# medusa-charger.net
KiCad netlist of a schematic drawn in Altium Designer
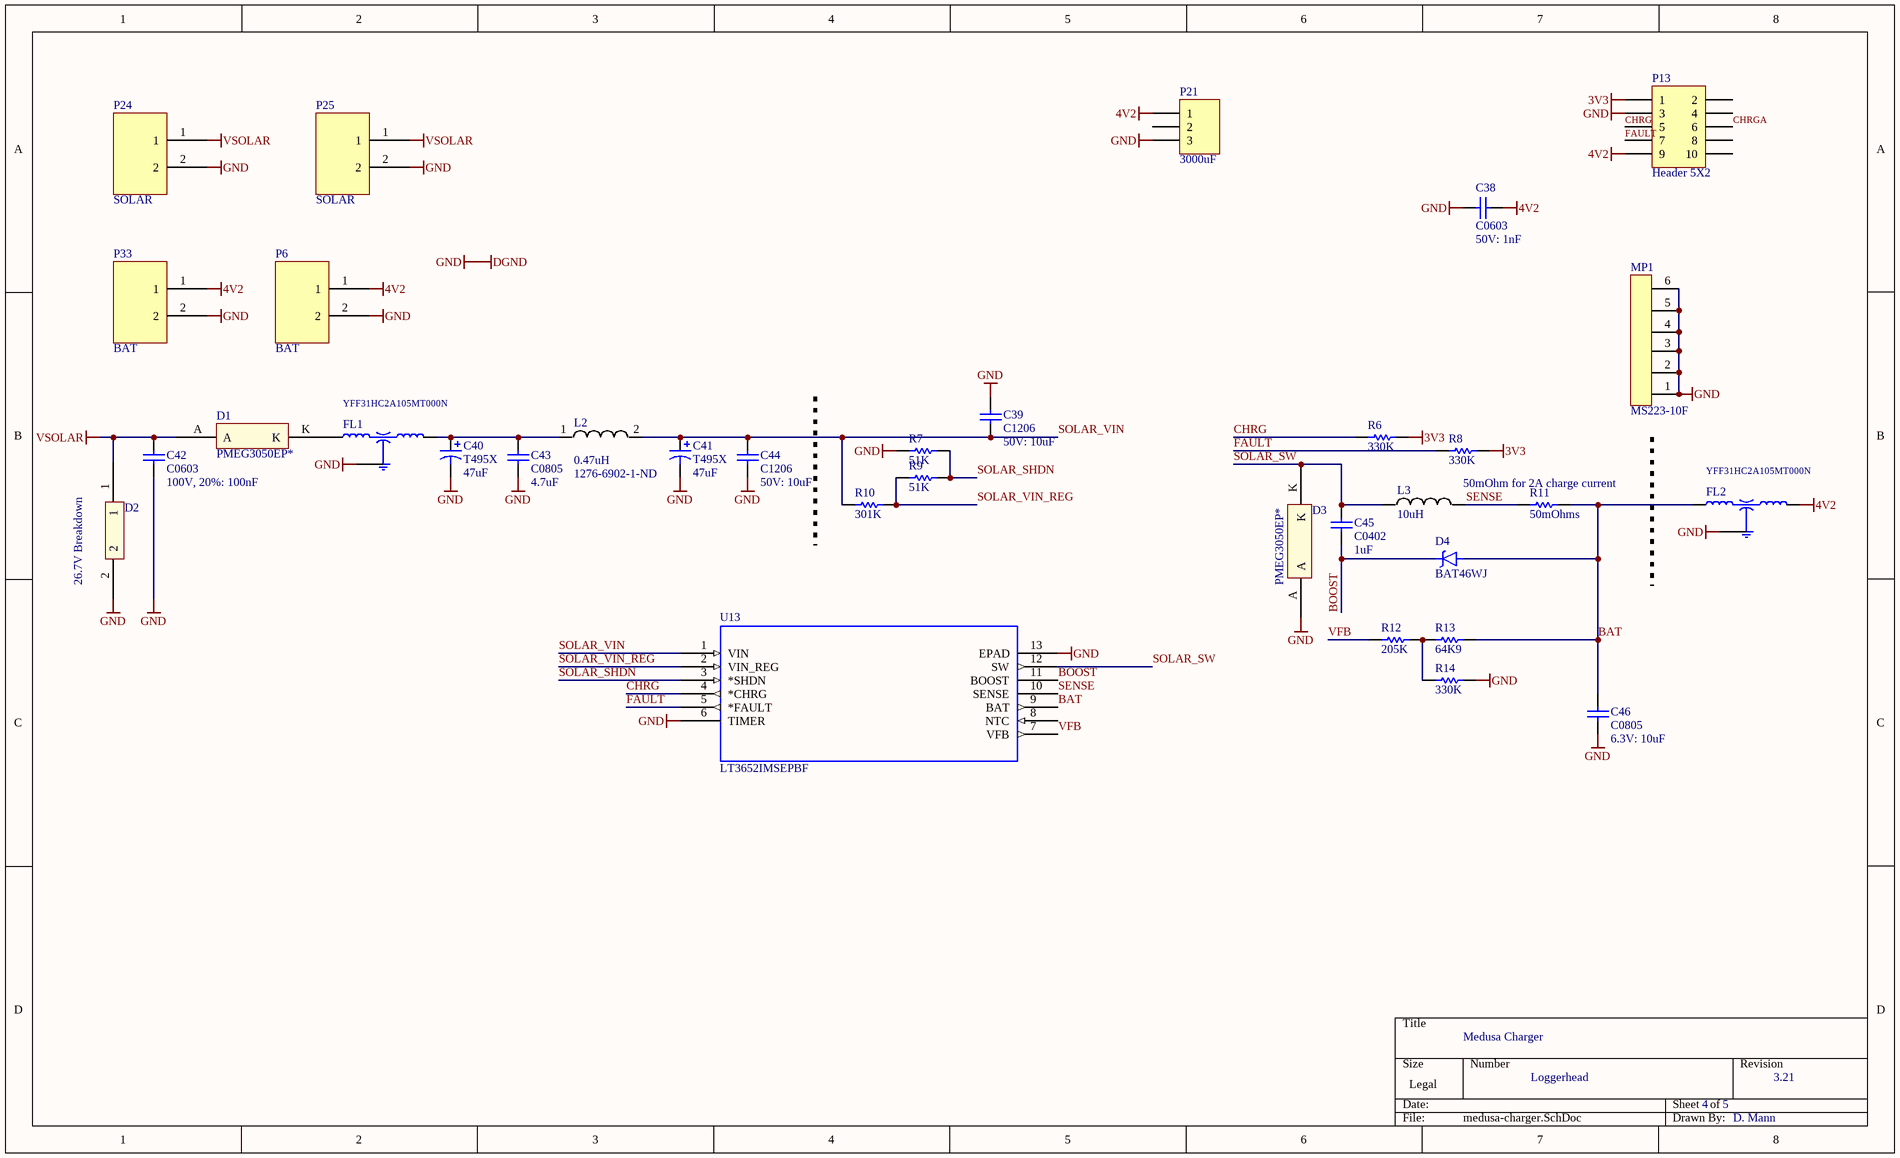
[diagram p0: medusa-charger.SchDoc]

(export (version "E")
  (design (tool "Eeschema 10.0.6"))
  (components
    (comp (ref "C38")
      (value "C0603")
      (footprint "0603")
      (description "Ceramic Chip Capacitor - Standard")
      (fields (field (name "50V") "1nF") (field (name "PUBLISHER") "Altium Limited"))
      (libsource (lib "KEMET Chip Capacitor") (part "C0603"))
    )
    (comp (ref "C39")
      (value "C1206")
      (footprint "1206")
      (description "Ceramic Chip Capacitor - Standard")
      (fields (field (name "50V") "10uF") (field (name "PUBLISHER") "Altium Limited"))
      (libsource (lib "KEMET Chip Capacitor") (part "C1206"))
    )
    (comp (ref "C40")
      (value "T495X")
      (footprint "X")
      (description "Solid Tantalum Chip Capacitor, Standard T495 Series - 35V 10%")
      (fields (field (name "ALTIUM_VALUE") "47uF") (field (name "PUBLISHER") "Altium Limited"))
      (libsource (lib "KEMET Chip Capacitor") (part "T495X"))
    )
    (comp (ref "C41")
      (value "T495X")
      (footprint "X")
      (description "Solid Tantalum Chip Capacitor, Standard T495 Series - 35V 10%")
      (fields (field (name "ALTIUM_VALUE") "47uF") (field (name "PUBLISHER") "Altium Limited"))
      (libsource (lib "KEMET Chip Capacitor") (part "T495X"))
    )
    (comp (ref "C42")
      (value "C0603")
      (footprint "0603")
      (description "100V 20%")
      (fields (field (name "100V, 20%") "100nF") (field (name "PUBLISHER") "Altium Limited"))
      (libsource (lib "KEMET Chip Capacitor") (part "C0603"))
    )
    (comp (ref "C43")
      (value "C0805")
      (footprint "0805")
      (description "Ceramic Chip Capacitor - Standard")
      (fields (field (name "ALTIUM_VALUE") "4.7uF") (field (name "PUBLISHER") "Altium Limited"))
      (libsource (lib "KEMET Chip Capacitor") (part "C0805"))
    )
    (comp (ref "C44")
      (value "C1206")
      (footprint "1206")
      (description "Ceramic Chip Capacitor - Standard")
      (fields (field (name "50V") "10uF") (field (name "PUBLISHER") "Altium Limited"))
      (libsource (lib "KEMET Chip Capacitor") (part "C1206"))
    )
    (comp (ref "C45")
      (value "C0402")
      (footprint "0402")
      (description "Ceramic Chip Capacitor - Standard")
      (fields (field (name "ALTIUM_VALUE") "1uF") (field (name "PUBLISHER") "Altium Limited"))
      (libsource (lib "KEMET Chip Capacitor") (part "C0402"))
    )
    (comp (ref "C46")
      (value "C0805")
      (footprint "0805")
      (description "Ceramic Chip Capacitor - Standard")
      (fields (field (name "6.3V") "10uF") (field (name "PUBLISHER") "Altium Limited"))
      (libsource (lib "KEMET Chip Capacitor") (part "C0805"))
    )
    (comp (ref "D1")
      (value "PMEG3050EP*")
      (footprint "Diode_PMEG3050EP")
      (libsource (lib "") (part "Diode_PMEG3050EP_1"))
    )
    (comp (ref "D2")
      (value "26.7V Breakdown")
      (footprint "SMBJ24CA")
      (libsource (lib "Loggerhead") (part "SMBJ24CA"))
    )
    (comp (ref "D3")
      (value "PMEG3050EP*")
      (footprint "Diode_PMEG3050EP")
      (libsource (lib "Loggerhead") (part "Diode_PMEG3050EP"))
    )
    (comp (ref "D4")
      (value "BAT46WJ")
      (footprint "SOD-323")
      (description "Diode Schottky 100V 250mA (DC) Surface Mount SOD-323F")
      (fields (field (name "MF") "NXP Semiconductors"))
      (libsource (lib "BAT46WJ") (part "BAT46WJ"))
    )
    (comp (ref "FL1")
      (value "YFF31HC2A105MT000N")
      (footprint "FIL_YFF31HC2A105MT000N")
      (description "1ÂµF Feed Through Capacitor 100V 6A 5mOhm 1206 (3216 Metric), 4 PC Pad")
      (fields (field (name "MF") "TDK"))
      (libsource (lib "YFF31HC2A105MT000N") (part "YFF31HC2A105MT000N"))
    )
    (comp (ref "FL2")
      (value "YFF31HC2A105MT000N")
      (footprint "FIL_YFF31HC2A105MT000N")
      (description "1ÂµF Feed Through Capacitor 100V 6A 5mOhm 1206 (3216 Metric), 4 PC Pad")
      (fields (field (name "MF") "TDK"))
      (libsource (lib "YFF31HC2A105MT000N") (part "YFF31HC2A105MT000N"))
    )
    (comp (ref "L2")
      (value "0.47uH")
      (footprint "Inductor2016")
      (fields
        (field (name "SUPPLIER PART NUMBER 1") "1276-6902-1-ND")
        (field (name "Comment") "Inductor2016")
      )
      (libsource (lib "Loggerhead") (part "Inductor2016"))
    )
    (comp (ref "L3")
      (value "10uH")
      (footprint "Inductor0630CDMCD")
      (libsource (lib "Loggerhead") (part "Inductor_0630CDMCD"))
    )
    (comp (ref "MP1")
      (value "MS223-10F")
      (footprint "MS223-10F")
      (description "RF Shield")
      (libsource (lib "Loggerhead") (part "MS223-10F"))
    )
    (comp (ref "P6")
      (value "BAT")
      (footprint "HDR_2x1_2mm")
      (libsource (lib "Loggerhead") (part "HDR_2x1_2mm"))
    )
    (comp (ref "P13")
      (value "Header 5X2")
      (footprint "HDR2X5")
      (description "Header, 5-Pin, Dual row")
      (fields (field (name "PUBLISHER") "Altium Limited"))
      (libsource (lib "Miscellaneous Connectors") (part "Header 5X2"))
    )
    (comp (ref "P21")
      (value "3000uF")
      (footprint "HDR1X3")
      (description "Header, 3-Pin")
      (fields (field (name "PUBLISHER") "Altium Limited"))
      (libsource (lib "Miscellaneous Connectors") (part "Header 3"))
    )
    (comp (ref "P24")
      (value "SOLAR")
      (footprint "HDR_2x1_2mm")
      (libsource (lib "Loggerhead") (part "HDR_2x1_2mm"))
    )
    (comp (ref "P25")
      (value "SOLAR")
      (footprint "HDR_2x1_2mm")
      (libsource (lib "Loggerhead") (part "HDR_2x1_2mm"))
    )
    (comp (ref "P33")
      (value "BAT")
      (footprint "HDR_2x1_2mm")
      (libsource (lib "Loggerhead") (part "HDR_2x1_2mm"))
    )
    (comp (ref "R6")
      (value "330K")
      (footprint "3-0603")
      (fields (field (name "PUBLISHER") "Altium Limited"))
      (libsource (lib "Panasonic Resistor") (part "ERJ3EK"))
    )
    (comp (ref "R7")
      (value "51K")
      (footprint "3-0603")
      (fields (field (name "PUBLISHER") "Altium Limited"))
      (libsource (lib "Panasonic Resistor") (part "ERJ3EK"))
    )
    (comp (ref "R8")
      (value "330K")
      (footprint "3-0603")
      (fields (field (name "PUBLISHER") "Altium Limited"))
      (libsource (lib "Panasonic Resistor") (part "ERJ3EK"))
    )
    (comp (ref "R9")
      (value "51K")
      (footprint "3-0603")
      (fields (field (name "PUBLISHER") "Altium Limited"))
      (libsource (lib "Panasonic Resistor") (part "ERJ3EK"))
    )
    (comp (ref "R10")
      (value "301K")
      (footprint "3-0603")
      (fields (field (name "PUBLISHER") "Altium Limited"))
      (libsource (lib "Panasonic Resistor") (part "ERJ3EK"))
    )
    (comp (ref "R11")
      (value "50mOhms")
      (footprint "8-1206")
      (description "Precision Thick Film Chip Resistor, 10 Ohm to 2.2M Ohm Range, 1% Tolerance, 1206 Size, 0.125 W")
      (fields (field (name "PUBLISHER") "Altium Limited"))
      (libsource (lib "Panasonic Resistor") (part "ERJ8EN"))
    )
    (comp (ref "R12")
      (value "205K")
      (footprint "3-0603")
      (fields (field (name "PUBLISHER") "Altium Limited"))
      (libsource (lib "Panasonic Resistor") (part "ERJ3EK"))
    )
    (comp (ref "R13")
      (value "64K9")
      (footprint "3-0603")
      (fields (field (name "PUBLISHER") "Altium Limited"))
      (libsource (lib "Panasonic Resistor") (part "ERJ3EK"))
    )
    (comp (ref "R14")
      (value "330K")
      (footprint "3-0603")
      (fields (field (name "PUBLISHER") "Altium Limited"))
      (libsource (lib "Panasonic Resistor") (part "ERJ3EK"))
    )
    (comp (ref "U13")
      (value "LT3652IMSEPBF")
      (footprint "MSOP-12_MSE")
      (description "Battery Charger Li-Ion 2000mA 4.2V Automotive 12-Pin MSOP EP Tube")
      (fields (field (name "MP") "LT3652IMSE#PBF") (field (name "DIGI-KEY_PART_NUMBER") "LT3652IMSE#PBF-ND"))
      (libsource (lib "LT3652IMSEPBF") (part "LT3652IMSEPBF"))
    )
  )
  (nets
    (net (code "1") (name "/BAT") (class "Default")
      (node (ref "C46") (pin "2") (pinfunction "2_2") (pintype "passive"))
      (node (ref "D4") (pin "A") (pinfunction "A_A") (pintype "passive"))
      (node (ref "FL2") (pin "1") (pinfunction "IN/OUT_1") (pintype "passive"))
      (node (ref "R11") (pin "2") (pinfunction "2_2") (pintype "passive"))
      (node (ref "R13") (pin "1") (pinfunction "1_1") (pintype "passive"))
      (node (ref "U13") (pin "9") (pinfunction "BAT_9") (pintype "output"))
    )
    (net (code "2") (name "/BOOST") (class "Default")
      (node (ref "C45") (pin "1") (pinfunction "1_1") (pintype "passive"))
      (node (ref "D4") (pin "C") (pinfunction "C_C") (pintype "passive"))
      (node (ref "U13") (pin "11") (pinfunction "BOOST_11") (pintype "passive"))
    )
    (net (code "3") (name "/CHRG") (class "Default")
      (node (ref "P13") (pin "5") (pinfunction "5_5") (pintype "passive"))
      (node (ref "R6") (pin "2") (pinfunction "2_2") (pintype "passive"))
      (node (ref "U13") (pin "4") (pinfunction "*CHRG_4") (pintype "output"))
    )
    (net (code "4") (name "/CHRGA") (class "Default")
      (node (ref "P13") (pin "6") (pinfunction "6_6") (pintype "passive"))
    )
    (net (code "5") (name "/FAULT") (class "Default")
      (node (ref "P13") (pin "7") (pinfunction "7_7") (pintype "passive"))
      (node (ref "R8") (pin "2") (pinfunction "2_2") (pintype "passive"))
      (node (ref "U13") (pin "5") (pinfunction "*FAULT_5") (pintype "output"))
    )
    (net (code "6") (name "/SENSE") (class "Default")
      (node (ref "L3") (pin "2") (pinfunction "2_2") (pintype "passive"))
      (node (ref "R11") (pin "1") (pinfunction "1_1") (pintype "passive"))
      (node (ref "U13") (pin "10") (pinfunction "SENSE_10") (pintype "passive"))
    )
    (net (code "7") (name "/SOLAR_SHDN") (class "Default")
      (node (ref "R7") (pin "2") (pinfunction "2_2") (pintype "passive"))
      (node (ref "R9") (pin "2") (pinfunction "2_2") (pintype "passive"))
      (node (ref "U13") (pin "3") (pinfunction "*SHDN_3") (pintype "input"))
    )
    (net (code "8") (name "/SOLAR_SW") (class "Default")
      (node (ref "C45") (pin "2") (pinfunction "2_2") (pintype "passive"))
      (node (ref "D3") (pin "K") (pinfunction "K_K") (pintype "passive"))
      (node (ref "L3") (pin "1") (pinfunction "1_1") (pintype "passive"))
      (node (ref "U13") (pin "12") (pinfunction "SW_12") (pintype "output"))
    )
    (net (code "9") (name "/SOLAR_VIN") (class "Default")
      (node (ref "C39") (pin "2") (pinfunction "2_2") (pintype "passive"))
      (node (ref "C41") (pin "1") (pinfunction "1_1") (pintype "passive"))
      (node (ref "C44") (pin "2") (pinfunction "2_2") (pintype "passive"))
      (node (ref "L2") (pin "2") (pinfunction "2_2") (pintype "passive"))
      (node (ref "R10") (pin "1") (pinfunction "1_1") (pintype "passive"))
      (node (ref "U13") (pin "1") (pinfunction "VIN_1") (pintype "input"))
    )
    (net (code "10") (name "/SOLAR_VIN_REG") (class "Default")
      (node (ref "R10") (pin "2") (pinfunction "2_2") (pintype "passive"))
      (node (ref "R9") (pin "1") (pinfunction "1_1") (pintype "passive"))
      (node (ref "U13") (pin "2") (pinfunction "VIN_REG_2") (pintype "input"))
    )
    (net (code "11") (name "/VFB") (class "Default")
      (node (ref "R12") (pin "2") (pinfunction "2_2") (pintype "passive"))
      (node (ref "U13") (pin "7") (pinfunction "VFB_7") (pintype "output"))
    )
    (net (code "12") (name "3V3") (class "Default")
      (node (ref "P13") (pin "1") (pinfunction "1_1") (pintype "passive"))
      (node (ref "R6") (pin "1") (pinfunction "1_1") (pintype "passive"))
      (node (ref "R8") (pin "1") (pinfunction "1_1") (pintype "passive"))
    )
    (net (code "13") (name "4V2") (class "Default")
      (node (ref "C38") (pin "2") (pinfunction "2_2") (pintype "passive"))
      (node (ref "FL2") (pin "3") (pinfunction "OUT/IN_3") (pintype "passive"))
      (node (ref "P13") (pin "9") (pinfunction "9_9") (pintype "passive"))
      (node (ref "P21") (pin "1") (pinfunction "1_1") (pintype "passive"))
      (node (ref "P33") (pin "1") (pinfunction "1_1") (pintype "passive"))
      (node (ref "P6") (pin "1") (pinfunction "1_1") (pintype "passive"))
    )
    (net (code "14") (name "DGND") (class "Default")
      (node (ref "C38") (pin "1") (pinfunction "1_1") (pintype "passive"))
      (node (ref "C39") (pin "1") (pinfunction "1_1") (pintype "passive"))
      (node (ref "C40") (pin "2") (pinfunction "2_2") (pintype "passive"))
      (node (ref "C41") (pin "2") (pinfunction "2_2") (pintype "passive"))
      (node (ref "C42") (pin "1") (pinfunction "1_1") (pintype "passive"))
      (node (ref "C43") (pin "1") (pinfunction "1_1") (pintype "passive"))
      (node (ref "C44") (pin "1") (pinfunction "1_1") (pintype "passive"))
      (node (ref "C46") (pin "1") (pinfunction "1_1") (pintype "passive"))
      (node (ref "D2") (pin "2") (pinfunction "2_2") (pintype "passive"))
      (node (ref "D3") (pin "A") (pinfunction "A_A") (pintype "passive"))
      (node (ref "FL1") (pin "2_4") (pinfunction "GND_2_4") (pintype "power_in"))
      (node (ref "FL2") (pin "2_4") (pinfunction "GND_2_4") (pintype "power_in"))
      (node (ref "MP1") (pin "1") (pinfunction "1_1") (pintype "passive"))
      (node (ref "MP1") (pin "2") (pinfunction "2_2") (pintype "passive"))
      (node (ref "MP1") (pin "3") (pinfunction "3_3") (pintype "passive"))
      (node (ref "MP1") (pin "4") (pinfunction "4_4") (pintype "passive"))
      (node (ref "MP1") (pin "5") (pinfunction "5_5") (pintype "passive"))
      (node (ref "MP1") (pin "6") (pinfunction "6_6") (pintype "passive"))
      (node (ref "P13") (pin "3") (pinfunction "3_3") (pintype "passive"))
      (node (ref "P21") (pin "3") (pinfunction "3_3") (pintype "passive"))
      (node (ref "P24") (pin "2") (pinfunction "2_2") (pintype "passive"))
      (node (ref "P25") (pin "2") (pinfunction "2_2") (pintype "passive"))
      (node (ref "P33") (pin "2") (pinfunction "2_2") (pintype "passive"))
      (node (ref "P6") (pin "2") (pinfunction "2_2") (pintype "passive"))
      (node (ref "R14") (pin "1") (pinfunction "1_1") (pintype "passive"))
      (node (ref "R7") (pin "1") (pinfunction "1_1") (pintype "passive"))
      (node (ref "U13") (pin "13") (pinfunction "EPAD_13") (pintype "passive"))
      (node (ref "U13") (pin "6") (pinfunction "TIMER_6") (pintype "passive"))
    )
    (net (code "15") (name "Net-(FL1-IN{slash}OUT)") (class "Default")
      (node (ref "D1") (pin "K") (pinfunction "K_K") (pintype "passive"))
      (node (ref "FL1") (pin "1") (pinfunction "IN/OUT_1") (pintype "passive"))
    )
    (net (code "16") (name "Net-(FL1-OUT{slash}IN)") (class "Default")
      (node (ref "C40") (pin "1") (pinfunction "1_1") (pintype "passive"))
      (node (ref "C43") (pin "2") (pinfunction "2_2") (pintype "passive"))
      (node (ref "FL1") (pin "3") (pinfunction "OUT/IN_3") (pintype "passive"))
      (node (ref "L2") (pin "1") (pinfunction "1_1") (pintype "passive"))
    )
    (net (code "17") (name "Net-(R12-Pad1)") (class "Default")
      (node (ref "R12") (pin "1") (pinfunction "1_1") (pintype "passive"))
      (node (ref "R13") (pin "2") (pinfunction "2_2") (pintype "passive"))
      (node (ref "R14") (pin "2") (pinfunction "2_2") (pintype "passive"))
    )
    (net (code "18") (name "VSOLAR") (class "Default")
      (node (ref "C42") (pin "2") (pinfunction "2_2") (pintype "passive"))
      (node (ref "D1") (pin "A") (pinfunction "A_A") (pintype "passive"))
      (node (ref "D2") (pin "1") (pinfunction "1_1") (pintype "passive"))
      (node (ref "P24") (pin "1") (pinfunction "1_1") (pintype "passive"))
      (node (ref "P25") (pin "1") (pinfunction "1_1") (pintype "passive"))
    )
    (net (code "19") (name "unconnected-(P13-Pad2)") (class "Default")
      (node (ref "P13") (pin "2") (pinfunction "2_2") (pintype "passive"))
    )
    (net (code "20") (name "unconnected-(P13-Pad4)") (class "Default")
      (node (ref "P13") (pin "4") (pinfunction "4_4") (pintype "passive"))
    )
    (net (code "21") (name "unconnected-(P13-Pad8)") (class "Default")
      (node (ref "P13") (pin "8") (pinfunction "8_8") (pintype "passive"))
    )
    (net (code "22") (name "unconnected-(P13-Pad10)") (class "Default")
      (node (ref "P13") (pin "10") (pinfunction "10_10") (pintype "passive"))
    )
    (net (code "23") (name "unconnected-(P21-Pad2)") (class "Default")
      (node (ref "P21") (pin "2") (pinfunction "2_2") (pintype "passive"))
    )
    (net (code "24") (name "unconnected-(U13-NTC-Pad8)") (class "Default")
      (node (ref "U13") (pin "8") (pinfunction "NTC_8") (pintype "input"))
    )
  )
)
